# ad.net
KiCad netlist of a schematic drawn in Altium Designer
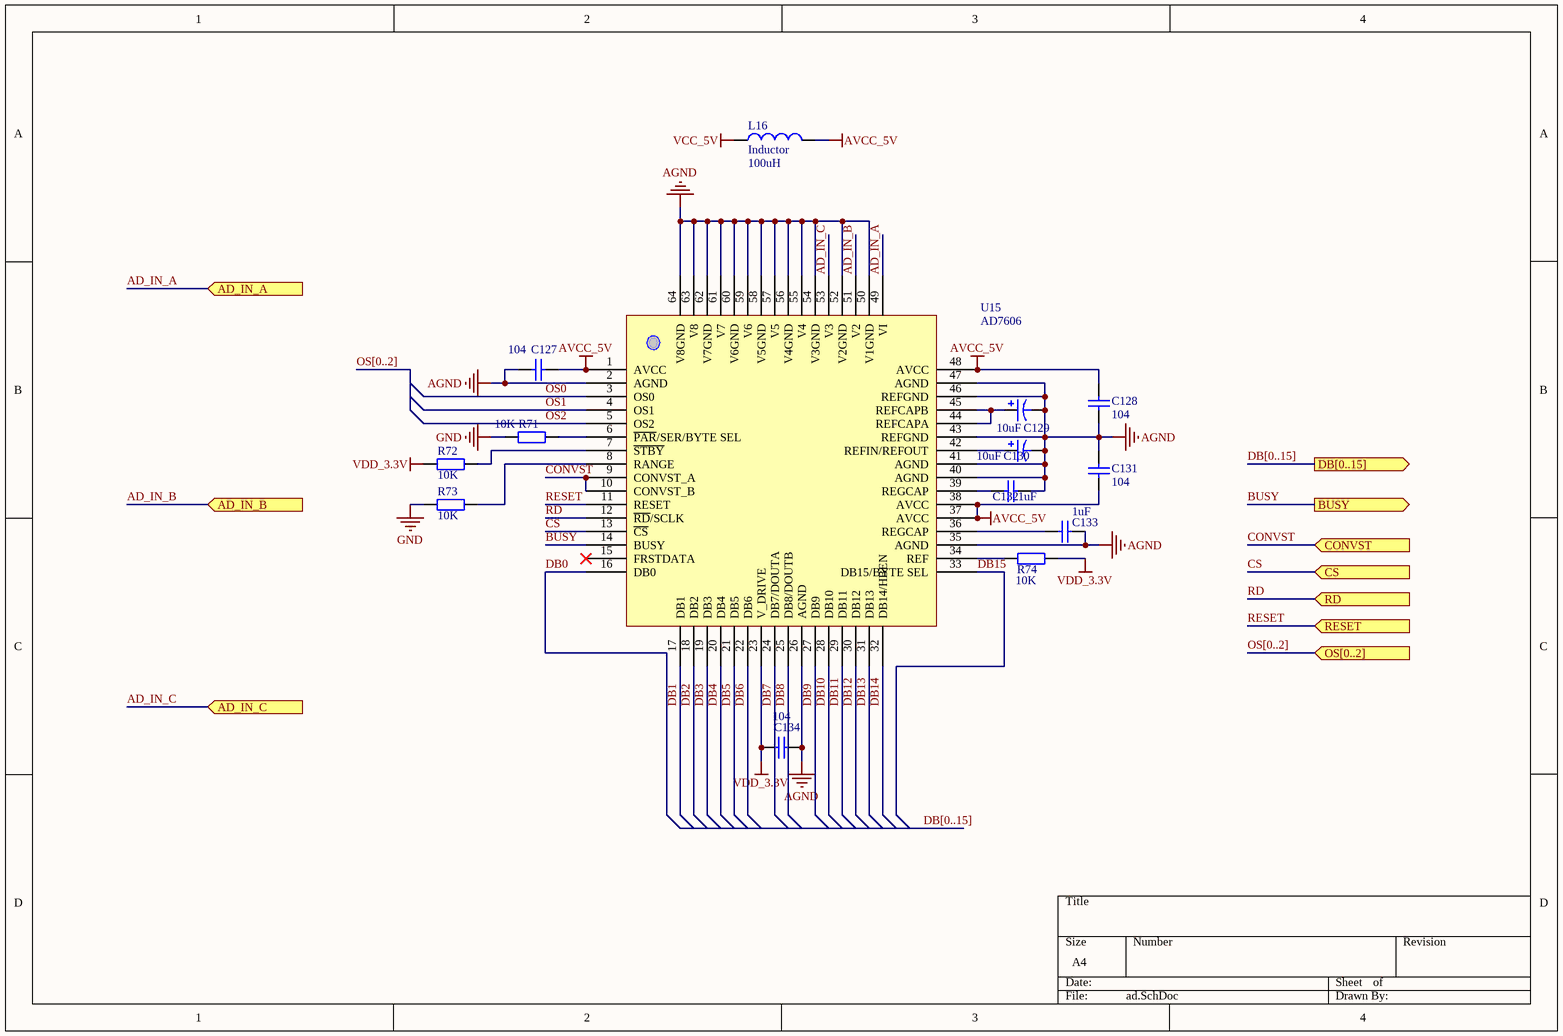
[diagram p0: ad.SchDoc]

(export (version "E")
  (design (tool "Eeschema 10.0.6"))
  (components
    (comp (ref "C127")
      (value "104")
      (footprint "0603")
      (fields
        (field (name "Comment") "Cap")
        (field (name "原理图绘制者") "刘永钦")
        (field (name "原理图提供者") "刘永钦")
        (field (name "原理图审核人1") "徐鹏飞")
        (field (name "封装0805绘制者") "刘永钦")
        (field (name "封装0805提供者") "刘永钦")
        (field (name "封装0805审核人1") "徐鹏飞")
        (field (name "原理图审核人2") "朱觉文")
        (field (name "封装0805审核人2") "朱觉文")
        (field (name "封装0603绘制者") "刘永钦")
        (field (name "封装0603提供者") "刘永钦")
        (field (name "封装0603审核人1") "朱觉文")
        (field (name "封装0603审核人2") "徐鹏飞")
      )
      (libsource (lib "自动化研究所集成库20170318") (part "Cap"))
    )
    (comp (ref "C128")
      (value "104")
      (footprint "0603")
      (fields
        (field (name "Comment") "Cap")
        (field (name "原理图绘制者") "刘永钦")
        (field (name "原理图提供者") "刘永钦")
        (field (name "原理图审核人1") "徐鹏飞")
        (field (name "封装0805绘制者") "刘永钦")
        (field (name "封装0805提供者") "刘永钦")
        (field (name "封装0805审核人1") "徐鹏飞")
        (field (name "原理图审核人2") "朱觉文")
        (field (name "封装0805审核人2") "朱觉文")
        (field (name "封装0603绘制者") "刘永钦")
        (field (name "封装0603提供者") "刘永钦")
        (field (name "封装0603审核人1") "朱觉文")
        (field (name "封装0603审核人2") "徐鹏飞")
      )
      (libsource (lib "自动化研究所集成库20170318") (part "Cap"))
    )
    (comp (ref "C129")
      (value "10uF")
      (footprint "Cap 3528B")
      (fields
        (field (name "Comment") "Cap Poll")
        (field (name "原理图绘制者") "刘永钦")
        (field (name "原理图提供者") "刘永钦")
        (field (name "原理图审核人1") "徐鹏飞")
        (field (name "封装CAP 钽 7343 E绘制者") "刘永钦")
        (field (name "封装CAP 钽 7343 E提供者") "刘永钦")
        (field (name "封装CAP 钽 7343 E审核人1") "徐鹏飞")
        (field (name "封装CAP贴片铝电解质470UF 16V绘制者") "李泽")
        (field (name "封装CAP贴片铝电解质470UF 16V提供者") "刘永钦")
        (field (name "封装CAP贴片铝电解质470UF 16V审核人1") "徐鹏飞")
        (field (name "封装CAP 3528B绘制者") "陈汉诚")
        (field (name "封装CAP 3528B提供者") "刘永钦")
        (field (name "封装CAP 3528B审核人1") "徐鹏飞")
        (field (name "封装CAP直插 10UF 50V提供者") "刘永钦")
        (field (name "封装CAP直插 10UF 50V审核人1") "徐鹏飞")
        (field (name "封装CAP 3528B审核人2") "朱觉文")
        (field (name "封装CAP直插 10UF 50V审核人2") "朱觉文")
        (field (name "封装CAP贴片铝电解质470UF 16V审核人2") "朱觉文")
        (field (name "封装CAP 钽 7343 E审核人2") "朱觉文")
        (field (name "原理图审核人2") "朱觉文")
      )
      (libsource (lib "自动化研究所集成库20170318") (part "Cap Poll"))
    )
    (comp (ref "C130")
      (value "10uF")
      (footprint "Cap 3528B")
      (fields
        (field (name "Comment") "Cap Poll")
        (field (name "原理图绘制者") "刘永钦")
        (field (name "原理图提供者") "刘永钦")
        (field (name "原理图审核人1") "徐鹏飞")
        (field (name "封装CAP 钽 7343 E绘制者") "刘永钦")
        (field (name "封装CAP 钽 7343 E提供者") "刘永钦")
        (field (name "封装CAP 钽 7343 E审核人1") "徐鹏飞")
        (field (name "封装CAP贴片铝电解质470UF 16V绘制者") "李泽")
        (field (name "封装CAP贴片铝电解质470UF 16V提供者") "刘永钦")
        (field (name "封装CAP贴片铝电解质470UF 16V审核人1") "徐鹏飞")
        (field (name "封装CAP 3528B绘制者") "陈汉诚")
        (field (name "封装CAP 3528B提供者") "刘永钦")
        (field (name "封装CAP 3528B审核人1") "徐鹏飞")
        (field (name "封装CAP直插 10UF 50V提供者") "刘永钦")
        (field (name "封装CAP直插 10UF 50V审核人1") "徐鹏飞")
        (field (name "封装CAP 3528B审核人2") "朱觉文")
        (field (name "封装CAP直插 10UF 50V审核人2") "朱觉文")
        (field (name "封装CAP贴片铝电解质470UF 16V审核人2") "朱觉文")
        (field (name "封装CAP 钽 7343 E审核人2") "朱觉文")
        (field (name "原理图审核人2") "朱觉文")
      )
      (libsource (lib "自动化研究所集成库20170318") (part "Cap Poll"))
    )
    (comp (ref "C131")
      (value "104")
      (footprint "0603")
      (fields
        (field (name "Comment") "Cap")
        (field (name "原理图绘制者") "刘永钦")
        (field (name "原理图提供者") "刘永钦")
        (field (name "原理图审核人1") "徐鹏飞")
        (field (name "封装0805绘制者") "刘永钦")
        (field (name "封装0805提供者") "刘永钦")
        (field (name "封装0805审核人1") "徐鹏飞")
        (field (name "原理图审核人2") "朱觉文")
        (field (name "封装0805审核人2") "朱觉文")
        (field (name "封装0603绘制者") "刘永钦")
        (field (name "封装0603提供者") "刘永钦")
        (field (name "封装0603审核人1") "朱觉文")
        (field (name "封装0603审核人2") "徐鹏飞")
      )
      (libsource (lib "自动化研究所集成库20170318") (part "Cap"))
    )
    (comp (ref "C132")
      (value "1uF")
      (footprint "0603")
      (fields
        (field (name "Comment") "Cap")
        (field (name "原理图绘制者") "刘永钦")
        (field (name "原理图提供者") "刘永钦")
        (field (name "原理图审核人1") "徐鹏飞")
        (field (name "封装0805绘制者") "刘永钦")
        (field (name "封装0805提供者") "刘永钦")
        (field (name "封装0805审核人1") "徐鹏飞")
        (field (name "原理图审核人2") "朱觉文")
        (field (name "封装0805审核人2") "朱觉文")
        (field (name "封装0603绘制者") "刘永钦")
        (field (name "封装0603提供者") "刘永钦")
        (field (name "封装0603审核人1") "朱觉文")
        (field (name "封装0603审核人2") "徐鹏飞")
      )
      (libsource (lib "自动化研究所集成库20170318") (part "Cap"))
    )
    (comp (ref "C133")
      (value "1uF")
      (footprint "0603")
      (fields
        (field (name "Comment") "Cap")
        (field (name "原理图绘制者") "刘永钦")
        (field (name "原理图提供者") "刘永钦")
        (field (name "原理图审核人1") "徐鹏飞")
        (field (name "封装0805绘制者") "刘永钦")
        (field (name "封装0805提供者") "刘永钦")
        (field (name "封装0805审核人1") "徐鹏飞")
        (field (name "原理图审核人2") "朱觉文")
        (field (name "封装0805审核人2") "朱觉文")
        (field (name "封装0603绘制者") "刘永钦")
        (field (name "封装0603提供者") "刘永钦")
        (field (name "封装0603审核人1") "朱觉文")
        (field (name "封装0603审核人2") "徐鹏飞")
      )
      (libsource (lib "自动化研究所集成库20170318") (part "Cap"))
    )
    (comp (ref "C134")
      (value "104")
      (footprint "0603")
      (fields
        (field (name "Comment") "Cap")
        (field (name "原理图绘制者") "刘永钦")
        (field (name "原理图提供者") "刘永钦")
        (field (name "原理图审核人1") "徐鹏飞")
        (field (name "封装0805绘制者") "刘永钦")
        (field (name "封装0805提供者") "刘永钦")
        (field (name "封装0805审核人1") "徐鹏飞")
        (field (name "原理图审核人2") "朱觉文")
        (field (name "封装0805审核人2") "朱觉文")
        (field (name "封装0603绘制者") "刘永钦")
        (field (name "封装0603提供者") "刘永钦")
        (field (name "封装0603审核人1") "朱觉文")
        (field (name "封装0603审核人2") "徐鹏飞")
      )
      (libsource (lib "自动化研究所集成库20170318") (part "Cap"))
    )
    (comp (ref "L16")
      (value "Inductor")
      (footprint "0805_Inductor")
      (fields
        (field (name "ALTIUM_VALUE") "100uH")
        (field (name "原理图绘制者") "刘永钦")
        (field (name "原理图提供者") "刘永钦")
        (field (name "原理图审核人1") "徐鹏飞")
        (field (name "封装0805_INDUCTOR绘制者") "未知")
        (field (name "封装0805_INDUCTOR提供者") "刘永钦")
        (field (name "封装0805_INDUCTOR审核人1") "徐鹏飞")
        (field (name "原理图审核人2") "朱觉文")
        (field (name "封装0805_INDUCTOR审核人2") "朱觉文")
      )
      (libsource (lib "自动化研究所集成库20170318") (part "Inductor"))
    )
    (comp (ref "R71")
      (value "10K")
      (footprint "0603")
      (fields
        (field (name "Comment") "Res")
        (field (name "原理图绘制者") "刘永钦")
        (field (name "原理图提供者") "刘永钦")
        (field (name "原理图审核人1") "徐鹏飞")
        (field (name "封装0805绘制者") "刘永钦")
        (field (name "封装0805提供者") "刘永钦")
        (field (name "封装0805审核人1") "徐鹏飞")
        (field (name "原理图审核人2") "朱觉文")
        (field (name "封装0805审核人2") "朱觉文")
        (field (name "封装0603提供者") "刘永钦")
        (field (name "封装0603审核人2") "朱觉文")
        (field (name "封装0603审核人1") "徐鹏飞")
        (field (name "封装2512-RESC6332X06N审核人2") "朱觉文")
        (field (name "封装2512-RESC6332X06N提供者") "刘永钦")
        (field (name "封装2512-RESC6332X06N审核人1") "徐鹏飞")
        (field (name "封装0603绘制者") "刘永钦")
        (field (name "封装2512-RESC6332X06N绘制者") "刘永钦")
      )
      (libsource (lib "自动化研究所集成库20170318") (part "Res"))
    )
    (comp (ref "R72")
      (value "10K")
      (footprint "0603")
      (fields
        (field (name "Comment") "Res")
        (field (name "原理图绘制者") "刘永钦")
        (field (name "原理图提供者") "刘永钦")
        (field (name "原理图审核人1") "徐鹏飞")
        (field (name "封装0805绘制者") "刘永钦")
        (field (name "封装0805提供者") "刘永钦")
        (field (name "封装0805审核人1") "徐鹏飞")
        (field (name "原理图审核人2") "朱觉文")
        (field (name "封装0805审核人2") "朱觉文")
        (field (name "封装0603提供者") "刘永钦")
        (field (name "封装0603审核人2") "朱觉文")
        (field (name "封装0603审核人1") "徐鹏飞")
        (field (name "封装2512-RESC6332X06N审核人2") "朱觉文")
        (field (name "封装2512-RESC6332X06N提供者") "刘永钦")
        (field (name "封装2512-RESC6332X06N审核人1") "徐鹏飞")
        (field (name "封装0603绘制者") "刘永钦")
        (field (name "封装2512-RESC6332X06N绘制者") "刘永钦")
      )
      (libsource (lib "自动化研究所集成库20170318") (part "Res"))
    )
    (comp (ref "R73")
      (value "10K")
      (footprint "0603")
      (fields
        (field (name "Comment") "Res")
        (field (name "原理图绘制者") "刘永钦")
        (field (name "原理图提供者") "刘永钦")
        (field (name "原理图审核人1") "徐鹏飞")
        (field (name "封装0805绘制者") "刘永钦")
        (field (name "封装0805提供者") "刘永钦")
        (field (name "封装0805审核人1") "徐鹏飞")
        (field (name "原理图审核人2") "朱觉文")
        (field (name "封装0805审核人2") "朱觉文")
        (field (name "封装0603提供者") "刘永钦")
        (field (name "封装0603审核人2") "朱觉文")
        (field (name "封装0603审核人1") "徐鹏飞")
        (field (name "封装2512-RESC6332X06N审核人2") "朱觉文")
        (field (name "封装2512-RESC6332X06N提供者") "刘永钦")
        (field (name "封装2512-RESC6332X06N审核人1") "徐鹏飞")
        (field (name "封装0603绘制者") "刘永钦")
        (field (name "封装2512-RESC6332X06N绘制者") "刘永钦")
      )
      (libsource (lib "自动化研究所集成库20170318") (part "Res"))
    )
    (comp (ref "R74")
      (value "10K")
      (footprint "0603")
      (fields
        (field (name "Comment") "Res")
        (field (name "原理图绘制者") "刘永钦")
        (field (name "原理图提供者") "刘永钦")
        (field (name "原理图审核人1") "徐鹏飞")
        (field (name "封装0805绘制者") "刘永钦")
        (field (name "封装0805提供者") "刘永钦")
        (field (name "封装0805审核人1") "徐鹏飞")
        (field (name "原理图审核人2") "朱觉文")
        (field (name "封装0805审核人2") "朱觉文")
        (field (name "封装0603提供者") "刘永钦")
        (field (name "封装0603审核人2") "朱觉文")
        (field (name "封装0603审核人1") "徐鹏飞")
        (field (name "封装2512-RESC6332X06N审核人2") "朱觉文")
        (field (name "封装2512-RESC6332X06N提供者") "刘永钦")
        (field (name "封装2512-RESC6332X06N审核人1") "徐鹏飞")
        (field (name "封装0603绘制者") "刘永钦")
        (field (name "封装2512-RESC6332X06N绘制者") "刘永钦")
      )
      (libsource (lib "自动化研究所集成库20170318") (part "Res"))
    )
    (comp (ref "U15")
      (value "AD7606")
      (footprint "TSQFP50P1200X1200X160-64N")
      (libsource (lib "Dugu") (part "AD7606"))
    )
  )
  (nets
    (net (code "1") (name "/AD_IN_A") (class "Default")
      (node (ref "U15") (pin "49") (pinfunction "VI_49") (pintype "passive"))
    )
    (net (code "2") (name "/AD_IN_B") (class "Default")
      (node (ref "U15") (pin "51") (pinfunction "V2_51") (pintype "passive"))
    )
    (net (code "3") (name "/AD_IN_C") (class "Default")
      (node (ref "U15") (pin "53") (pinfunction "V3_53") (pintype "passive"))
    )
    (net (code "4") (name "/BUSY") (class "Default")
      (node (ref "U15") (pin "14") (pinfunction "BUSY_14") (pintype "passive"))
    )
    (net (code "5") (name "/CONVST") (class "Default")
      (node (ref "U15") (pin "10") (pinfunction "CONVST_B_10") (pintype "passive"))
      (node (ref "U15") (pin "9") (pinfunction "CONVST_A_9") (pintype "passive"))
    )
    (net (code "6") (name "/CS") (class "Default")
      (node (ref "U15") (pin "13") (pinfunction "~{CS}_13") (pintype "passive"))
    )
    (net (code "7") (name "/DB0") (class "Default")
      (node (ref "U15") (pin "16") (pinfunction "DB0_16") (pintype "passive"))
    )
    (net (code "8") (name "/DB1") (class "Default")
      (node (ref "U15") (pin "17") (pinfunction "DB1_17") (pintype "passive"))
    )
    (net (code "9") (name "/DB2") (class "Default")
      (node (ref "U15") (pin "18") (pinfunction "DB2_18") (pintype "passive"))
    )
    (net (code "10") (name "/DB3") (class "Default")
      (node (ref "U15") (pin "19") (pinfunction "DB3_19") (pintype "passive"))
    )
    (net (code "11") (name "/DB4") (class "Default")
      (node (ref "U15") (pin "20") (pinfunction "DB4_20") (pintype "passive"))
    )
    (net (code "12") (name "/DB5") (class "Default")
      (node (ref "U15") (pin "21") (pinfunction "DB5_21") (pintype "passive"))
    )
    (net (code "13") (name "/DB6") (class "Default")
      (node (ref "U15") (pin "22") (pinfunction "DB6_22") (pintype "passive"))
    )
    (net (code "14") (name "/DB7") (class "Default")
      (node (ref "U15") (pin "24") (pinfunction "DB7/DOUTA_24") (pintype "passive"))
    )
    (net (code "15") (name "/DB8") (class "Default")
      (node (ref "U15") (pin "25") (pinfunction "DB8/DOUTB_25") (pintype "passive"))
    )
    (net (code "16") (name "/DB9") (class "Default")
      (node (ref "U15") (pin "27") (pinfunction "DB9_27") (pintype "passive"))
    )
    (net (code "17") (name "/DB10") (class "Default")
      (node (ref "U15") (pin "28") (pinfunction "DB10_28") (pintype "passive"))
    )
    (net (code "18") (name "/DB11") (class "Default")
      (node (ref "U15") (pin "29") (pinfunction "DB11_29") (pintype "passive"))
    )
    (net (code "19") (name "/DB12") (class "Default")
      (node (ref "U15") (pin "30") (pinfunction "DB12_30") (pintype "passive"))
    )
    (net (code "20") (name "/DB13") (class "Default")
      (node (ref "U15") (pin "31") (pinfunction "DB13_31") (pintype "passive"))
    )
    (net (code "21") (name "/DB14") (class "Default")
      (node (ref "U15") (pin "32") (pinfunction "DB14/HBEN_32") (pintype "passive"))
    )
    (net (code "22") (name "/DB15") (class "Default")
      (node (ref "U15") (pin "33") (pinfunction "DB15/BYTE_SEL_33") (pintype "passive"))
    )
    (net (code "24") (name "/OS0") (class "Default")
      (node (ref "U15") (pin "3") (pinfunction "OS0_3") (pintype "passive"))
    )
    (net (code "25") (name "/OS1") (class "Default")
      (node (ref "U15") (pin "4") (pinfunction "OS1_4") (pintype "passive"))
    )
    (net (code "26") (name "/OS2") (class "Default")
      (node (ref "U15") (pin "5") (pinfunction "OS2_5") (pintype "passive"))
    )
    (net (code "28") (name "/RD") (class "Default")
      (node (ref "U15") (pin "12") (pinfunction "~{RD}/SCLK_12") (pintype "passive"))
    )
    (net (code "29") (name "/RESET") (class "Default")
      (node (ref "U15") (pin "11") (pinfunction "RESET_11") (pintype "passive"))
    )
    (net (code "30") (name "AGND") (class "Default")
      (node (ref "C127") (pin "2") (pinfunction "2_2") (pintype "passive"))
      (node (ref "C128") (pin "2") (pinfunction "2_2") (pintype "passive"))
      (node (ref "C129") (pin "2") (pinfunction "2_2") (pintype "passive"))
      (node (ref "C130") (pin "2") (pinfunction "2_2") (pintype "passive"))
      (node (ref "C131") (pin "1") (pinfunction "1_1") (pintype "passive"))
      (node (ref "C132") (pin "1") (pinfunction "1_1") (pintype "passive"))
      (node (ref "C133") (pin "1") (pinfunction "1_1") (pintype "passive"))
      (node (ref "C134") (pin "1") (pinfunction "1_1") (pintype "passive"))
      (node (ref "U15") (pin "2") (pinfunction "AGND_2") (pintype "passive"))
      (node (ref "U15") (pin "26") (pinfunction "AGND_26") (pintype "passive"))
      (node (ref "U15") (pin "35") (pinfunction "AGND_35") (pintype "passive"))
      (node (ref "U15") (pin "40") (pinfunction "AGND_40") (pintype "passive"))
      (node (ref "U15") (pin "41") (pinfunction "AGND_41") (pintype "passive"))
      (node (ref "U15") (pin "43") (pinfunction "REFGND_43") (pintype "passive"))
      (node (ref "U15") (pin "46") (pinfunction "REFGND_46") (pintype "passive"))
      (node (ref "U15") (pin "47") (pinfunction "AGND_47") (pintype "passive"))
      (node (ref "U15") (pin "50") (pinfunction "V1GND_50") (pintype "passive"))
      (node (ref "U15") (pin "52") (pinfunction "V2GND_52") (pintype "passive"))
      (node (ref "U15") (pin "54") (pinfunction "V3GND_54") (pintype "passive"))
      (node (ref "U15") (pin "55") (pinfunction "V4_55") (pintype "passive"))
      (node (ref "U15") (pin "56") (pinfunction "V4GND_56") (pintype "passive"))
      (node (ref "U15") (pin "57") (pinfunction "V5_57") (pintype "passive"))
      (node (ref "U15") (pin "58") (pinfunction "V5GND_58") (pintype "passive"))
      (node (ref "U15") (pin "59") (pinfunction "V6_59") (pintype "passive"))
      (node (ref "U15") (pin "60") (pinfunction "V6GND_60") (pintype "passive"))
      (node (ref "U15") (pin "61") (pinfunction "V7_61") (pintype "passive"))
      (node (ref "U15") (pin "62") (pinfunction "V7GND_62") (pintype "passive"))
      (node (ref "U15") (pin "63") (pinfunction "V8_63") (pintype "passive"))
      (node (ref "U15") (pin "64") (pinfunction "V8GND_64") (pintype "passive"))
    )
    (net (code "31") (name "AVCC_5V") (class "Default")
      (node (ref "C127") (pin "1") (pinfunction "1_1") (pintype "passive"))
      (node (ref "C128") (pin "1") (pinfunction "1_1") (pintype "passive"))
      (node (ref "C131") (pin "2") (pinfunction "2_2") (pintype "passive"))
      (node (ref "L16") (pin "2") (pinfunction "2_2") (pintype "passive"))
      (node (ref "U15") (pin "1") (pinfunction "AVCC_1") (pintype "passive"))
      (node (ref "U15") (pin "37") (pinfunction "AVCC_37") (pintype "passive"))
      (node (ref "U15") (pin "38") (pinfunction "AVCC_38") (pintype "passive"))
      (node (ref "U15") (pin "48") (pinfunction "AVCC_48") (pintype "passive"))
    )
    (net (code "32") (name "GND") (class "Default")
      (node (ref "R71") (pin "1") (pinfunction "1_1") (pintype "passive"))
      (node (ref "R73") (pin "1") (pinfunction "1_1") (pintype "passive"))
    )
    (net (code "33") (name "Net-(C132-Pad2)") (class "Default")
      (node (ref "C132") (pin "2") (pinfunction "2_2") (pintype "passive"))
      (node (ref "U15") (pin "39") (pinfunction "REGCAP_39") (pintype "passive"))
    )
    (net (code "34") (name "Net-(C133-Pad2)") (class "Default")
      (node (ref "C133") (pin "2") (pinfunction "2_2") (pintype "passive"))
      (node (ref "U15") (pin "36") (pinfunction "REGCAP_36") (pintype "passive"))
    )
    (net (code "35") (name "Net-(U15-RANGE)") (class "Default")
      (node (ref "R73") (pin "2") (pinfunction "2_2") (pintype "passive"))
      (node (ref "U15") (pin "8") (pinfunction "RANGE_8") (pintype "passive"))
    )
    (net (code "36") (name "Net-(U15-REF)") (class "Default")
      (node (ref "R74") (pin "1") (pinfunction "1_1") (pintype "passive"))
      (node (ref "U15") (pin "34") (pinfunction "REF_34") (pintype "passive"))
    )
    (net (code "37") (name "Net-(U15-REFCAPA)") (class "Default")
      (node (ref "C129") (pin "1") (pinfunction "1_1") (pintype "passive"))
      (node (ref "U15") (pin "44") (pinfunction "REFCAPA_44") (pintype "passive"))
      (node (ref "U15") (pin "45") (pinfunction "REFCAPB_45") (pintype "passive"))
    )
    (net (code "38") (name "Net-(U15-REFIN{slash}REFOUT)") (class "Default")
      (node (ref "C130") (pin "1") (pinfunction "1_1") (pintype "passive"))
      (node (ref "U15") (pin "42") (pinfunction "REFIN/REFOUT_42") (pintype "passive"))
    )
    (net (code "39") (name "Net-(U15-~{PAR}{slash}SER{slash}BYTE_SEL)") (class "Default")
      (node (ref "R71") (pin "2") (pinfunction "2_2") (pintype "passive"))
      (node (ref "U15") (pin "6") (pinfunction "~{PAR}/SER/BYTE_SEL_6") (pintype "passive"))
    )
    (net (code "40") (name "Net-(U15-~{STBY})") (class "Default")
      (node (ref "R72") (pin "2") (pinfunction "2_2") (pintype "passive"))
      (node (ref "U15") (pin "7") (pinfunction "~{STBY}_7") (pintype "passive"))
    )
    (net (code "41") (name "VCC_5V") (class "Default")
      (node (ref "L16") (pin "1") (pinfunction "1_1") (pintype "passive"))
    )
    (net (code "42") (name "VDD_3.3V") (class "Default")
      (node (ref "C134") (pin "2") (pinfunction "2_2") (pintype "passive"))
      (node (ref "R72") (pin "1") (pinfunction "1_1") (pintype "passive"))
      (node (ref "R74") (pin "2") (pinfunction "2_2") (pintype "passive"))
      (node (ref "U15") (pin "23") (pinfunction "V_DRIVE_23") (pintype "passive"))
    )
    (net (code "43") (name "unconnected-(U15-FRSTDATA-Pad15)") (class "Default")
      (node (ref "U15") (pin "15") (pinfunction "FRSTDATA_15") (pintype "passive+no_connect"))
    )
  )
)
